# satstep2660.net
KiCad netlist of a schematic drawn in EAGLE
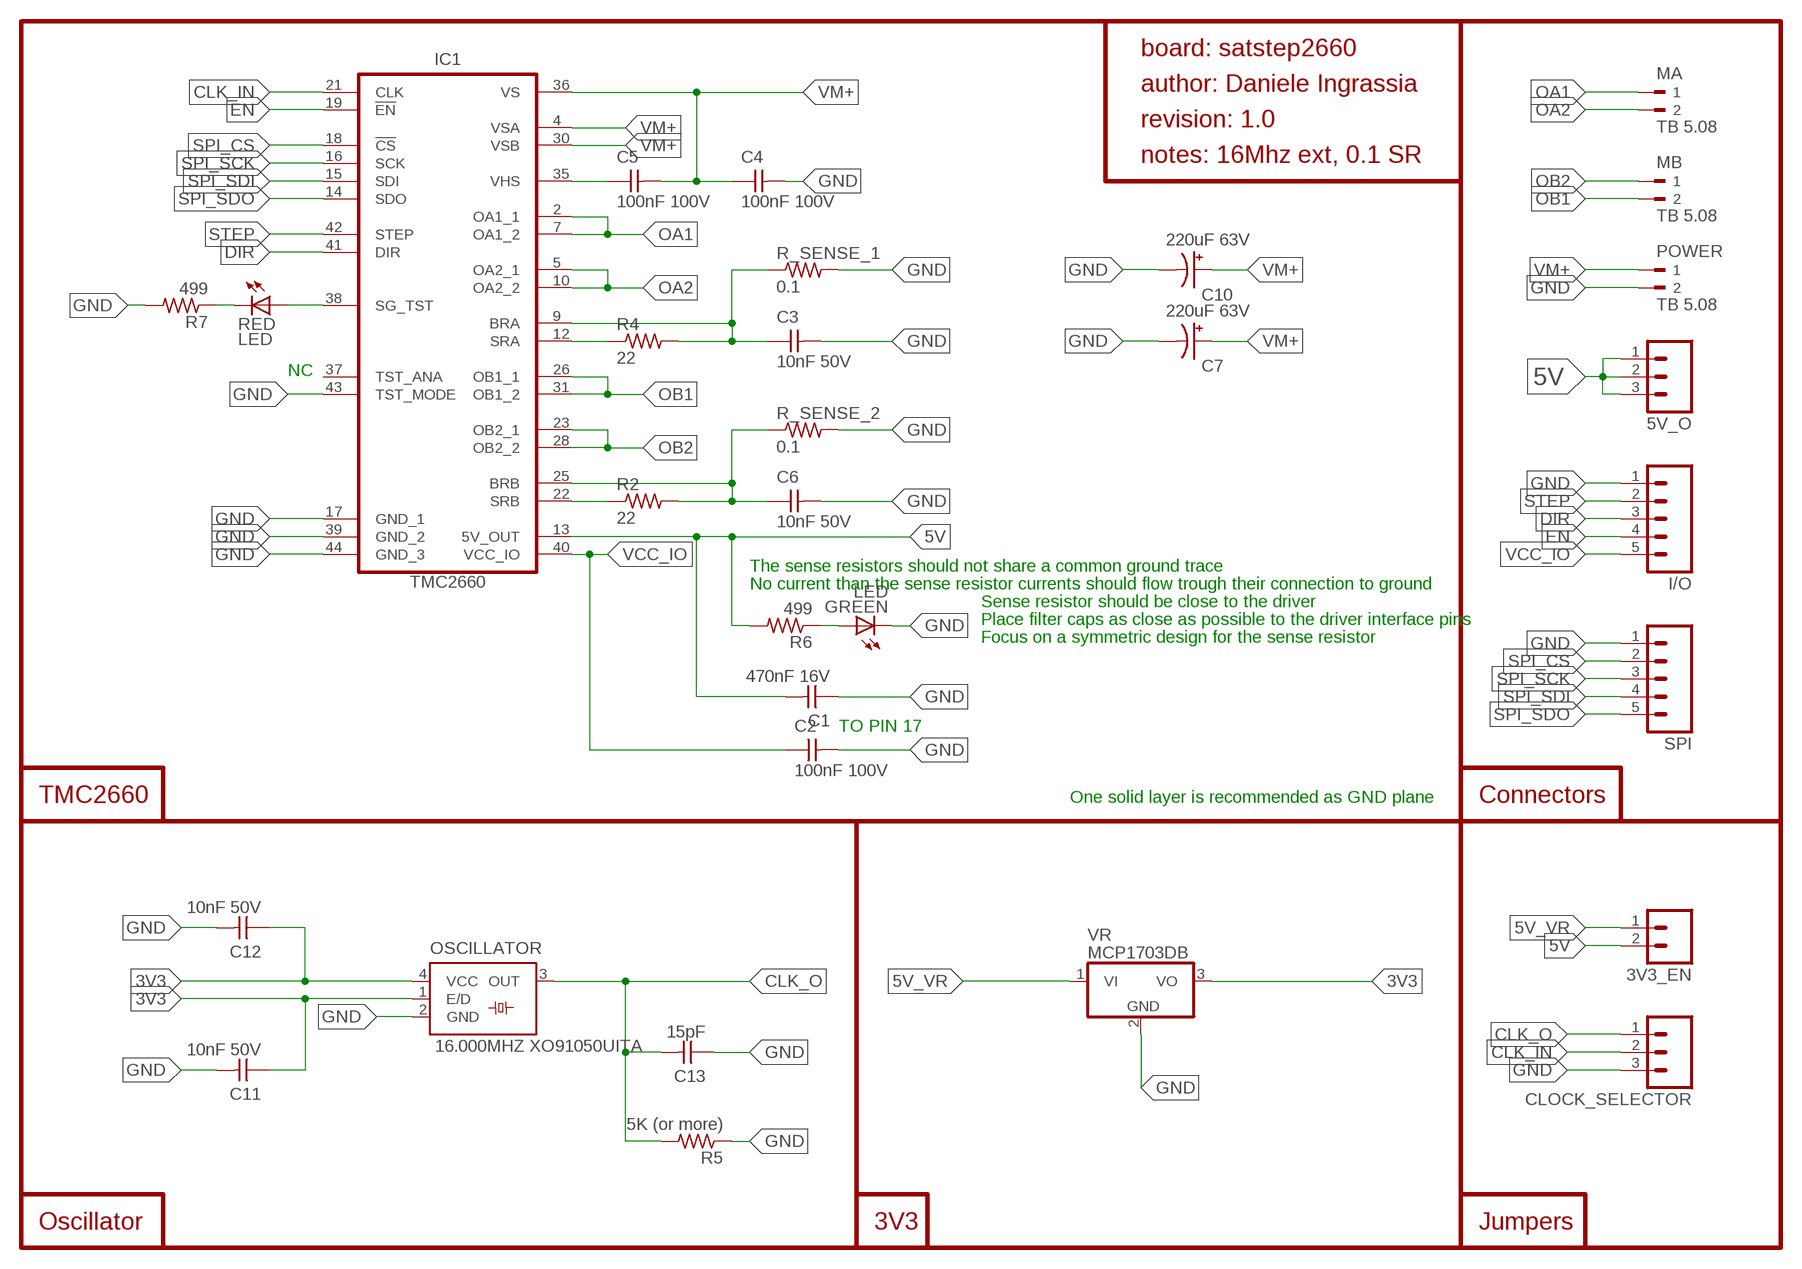
[diagram p0: schematic, sheet 1]

(export (version "E")
  (design (tool "Eeschema 10.0.6"))
  (components
    (comp (ref "3V3_EN")
      (value "M02")
      (footprint "eagle-import:02P")
      (libsource (lib "eagle-import") (part "M02"))
    )
    (comp (ref "5V_O")
      (value "M03")
      (footprint "eagle-import:03P")
      (libsource (lib "eagle-import") (part "M03"))
    )
    (comp (ref "C1")
      (value "470nF 16V")
      (footprint "eagle-import:C1206")
      (libsource (lib "eagle-import") (part "CAP-UNPOLARIZED"))
    )
    (comp (ref "C2")
      (value "100nF 100V")
      (footprint "eagle-import:C1206")
      (libsource (lib "eagle-import") (part "CAP-UNPOLARIZED"))
    )
    (comp (ref "C3")
      (value "10nF 50V")
      (footprint "eagle-import:C1206")
      (libsource (lib "eagle-import") (part "CAP-UNPOLARIZED"))
    )
    (comp (ref "C4")
      (value "100nF 100V")
      (footprint "eagle-import:C1206")
      (libsource (lib "eagle-import") (part "CAP-UNPOLARIZED"))
    )
    (comp (ref "C5")
      (value "100nF 100V")
      (footprint "eagle-import:C1206")
      (libsource (lib "eagle-import") (part "CAP-UNPOLARIZED"))
    )
    (comp (ref "C6")
      (value "10nF 50V")
      (footprint "eagle-import:C1206")
      (libsource (lib "eagle-import") (part "CAP-UNPOLARIZED"))
    )
    (comp (ref "C7")
      (value "220uF 63V")
      (footprint "eagle-import:CPOL-RADIAL-5MM-10MM")
      (libsource (lib "eagle-import") (part "1000UF-RADIAL-5MM-25V-20%"))
    )
    (comp (ref "C10")
      (value "220uF 63V")
      (footprint "eagle-import:CPOL-RADIAL-5MM-10MM")
      (libsource (lib "eagle-import") (part "1000UF-RADIAL-5MM-25V-20%"))
    )
    (comp (ref "C11")
      (value "10nF 50V")
      (footprint "eagle-import:C1206")
      (libsource (lib "eagle-import") (part "CAP-UNPOLARIZED"))
    )
    (comp (ref "C12")
      (value "10nF 50V")
      (footprint "eagle-import:C1206")
      (libsource (lib "eagle-import") (part "CAP-UNPOLARIZED"))
    )
    (comp (ref "C13")
      (value "15pF")
      (footprint "eagle-import:C1206")
      (libsource (lib "eagle-import") (part "CAP-UNPOLARIZED"))
    )
    (comp (ref "CLOCK_SELECTOR")
      (value "M03")
      (footprint "eagle-import:03P")
      (libsource (lib "eagle-import") (part "M03"))
    )
    (comp (ref "GREEN")
      (value "LED")
      (footprint "eagle-import:LED1206")
      (libsource (lib "eagle-import") (part "LED"))
    )
    (comp (ref "I/O")
      (value "M05")
      (footprint "eagle-import:05P")
      (libsource (lib "eagle-import") (part "M05"))
    )
    (comp (ref "IC1")
      (value "TMC2660")
      (footprint "eagle-import:TMC_PQFP44_0.8_10X10_TMC236")
      (fields (field (name "MANUFACTURER") " TRINAMIC "))
      (libsource (lib "eagle-import") (part "TMC2660-PA"))
    )
    (comp (ref "MA")
      (value "TB 5.08")
      (footprint "eagle-import:WEIDMULLER_PM5.08_2")
      (fields (field (name "MPN") "PM5.08/2/90 BLK"))
      (libsource (lib "eagle-import") (part "PM5.08/2/90BLK"))
    )
    (comp (ref "MB")
      (value "TB 5.08")
      (footprint "eagle-import:WEIDMULLER_PM5.08_2")
      (fields (field (name "MPN") "PM5.08/2/90 BLK"))
      (libsource (lib "eagle-import") (part "PM5.08/2/90BLK"))
    )
    (comp (ref "OSCILLATOR")
      (value "16.000MHZ XO91050UITA")
      (footprint "eagle-import:SM77H")
      (libsource (lib "eagle-import") (part "SM77H"))
    )
    (comp (ref "POWER")
      (value "TB 5.08")
      (footprint "eagle-import:WEIDMULLER_PM5.08_2")
      (fields (field (name "MPN") "PM5.08/2/90 BLK"))
      (libsource (lib "eagle-import") (part "PM5.08/2/90BLK"))
    )
    (comp (ref "R2")
      (value "22")
      (footprint "eagle-import:R1206")
      (libsource (lib "eagle-import") (part "RES-US1206"))
    )
    (comp (ref "R4")
      (value "22")
      (footprint "eagle-import:R1206")
      (libsource (lib "eagle-import") (part "RES-US1206"))
    )
    (comp (ref "R5")
      (value "5K (or more)")
      (footprint "eagle-import:R1206")
      (libsource (lib "eagle-import") (part "RES-US1206"))
    )
    (comp (ref "R6")
      (value "499")
      (footprint "eagle-import:R1206")
      (libsource (lib "eagle-import") (part "RES-US1206"))
    )
    (comp (ref "R7")
      (value "499")
      (footprint "eagle-import:R1206")
      (libsource (lib "eagle-import") (part "RES-US1206"))
    )
    (comp (ref "RED")
      (value "LED")
      (footprint "eagle-import:LED1206")
      (libsource (lib "eagle-import") (part "LED"))
    )
    (comp (ref "R_SENSE_1")
      (value "0.1")
      (footprint "eagle-import:R1206")
      (libsource (lib "eagle-import") (part "RES-US1206"))
    )
    (comp (ref "R_SENSE_2")
      (value "0.1")
      (footprint "eagle-import:R1206")
      (libsource (lib "eagle-import") (part "RES-US1206"))
    )
    (comp (ref "SPI")
      (value "M05")
      (footprint "eagle-import:05P")
      (libsource (lib "eagle-import") (part "M05"))
    )
    (comp (ref "VR")
      (value "MCP1703DB")
      (footprint "eagle-import:SOT223")
      (libsource (lib "eagle-import") (part "MCP1703DB"))
    )
  )
  (nets
    (net (code "1") (name "3V3") (class "Default")
      (node (ref "C11") (pin "1") (pinfunction "1_1") (pintype "passive"))
      (node (ref "C12") (pin "1") (pinfunction "1_1") (pintype "passive"))
      (node (ref "OSCILLATOR") (pin "1") (pinfunction "E/D_1") (pintype "input"))
      (node (ref "OSCILLATOR") (pin "4") (pinfunction "VCC_4") (pintype "power_in"))
      (node (ref "VR") (pin "3") (pinfunction "VO_3") (pintype "passive"))
    )
    (net (code "2") (name "5V") (class "Default")
      (node (ref "3V3_EN") (pin "2") (pinfunction "2_2") (pintype "passive"))
      (node (ref "5V_O") (pin "1") (pinfunction "1_1") (pintype "passive"))
      (node (ref "5V_O") (pin "2") (pinfunction "2_2") (pintype "passive"))
      (node (ref "5V_O") (pin "3") (pinfunction "3_3") (pintype "passive"))
      (node (ref "C1") (pin "2") (pinfunction "2_2") (pintype "passive"))
      (node (ref "IC1") (pin "13") (pinfunction "5V_OUT_13") (pintype "output"))
      (node (ref "R6") (pin "2") (pinfunction "2_2") (pintype "passive"))
    )
    (net (code "3") (name "5V_VR") (class "Default")
      (node (ref "3V3_EN") (pin "1") (pinfunction "1_1") (pintype "passive"))
      (node (ref "VR") (pin "1") (pinfunction "VI_1") (pintype "input"))
    )
    (net (code "4") (name "CLK_IN") (class "Default")
      (node (ref "CLOCK_SELECTOR") (pin "2") (pinfunction "2_2") (pintype "passive"))
      (node (ref "IC1") (pin "21") (pinfunction "CLK_21") (pintype "input"))
    )
    (net (code "5") (name "CLK_O") (class "Default")
      (node (ref "C13") (pin "2") (pinfunction "2_2") (pintype "passive"))
      (node (ref "CLOCK_SELECTOR") (pin "1") (pinfunction "1_1") (pintype "passive"))
      (node (ref "OSCILLATOR") (pin "3") (pinfunction "OUT_3") (pintype "output"))
      (node (ref "R5") (pin "2") (pinfunction "2_2") (pintype "passive"))
    )
    (net (code "6") (name "DIR") (class "Default")
      (node (ref "I/O") (pin "3") (pinfunction "3_3") (pintype "passive"))
      (node (ref "IC1") (pin "41") (pinfunction "DIR_41") (pintype "input"))
    )
    (net (code "7") (name "EN") (class "Default")
      (node (ref "I/O") (pin "4") (pinfunction "4_4") (pintype "passive"))
      (node (ref "IC1") (pin "19") (pinfunction "~{EN}_19") (pintype "input"))
    )
    (net (code "8") (name "GND") (class "Default")
      (node (ref "C1") (pin "1") (pinfunction "1_1") (pintype "passive"))
      (node (ref "C10") (pin "-") (pinfunction "-_-") (pintype "passive"))
      (node (ref "C11") (pin "2") (pinfunction "2_2") (pintype "passive"))
      (node (ref "C12") (pin "2") (pinfunction "2_2") (pintype "passive"))
      (node (ref "C13") (pin "1") (pinfunction "1_1") (pintype "passive"))
      (node (ref "C2") (pin "2") (pinfunction "2_2") (pintype "passive"))
      (node (ref "C3") (pin "2") (pinfunction "2_2") (pintype "passive"))
      (node (ref "C4") (pin "2") (pinfunction "2_2") (pintype "passive"))
      (node (ref "C6") (pin "2") (pinfunction "2_2") (pintype "passive"))
      (node (ref "C7") (pin "-") (pinfunction "-_-") (pintype "passive"))
      (node (ref "CLOCK_SELECTOR") (pin "3") (pinfunction "3_3") (pintype "passive"))
      (node (ref "GREEN") (pin "2") (pinfunction "C_2") (pintype "passive"))
      (node (ref "I/O") (pin "1") (pinfunction "1_1") (pintype "passive"))
      (node (ref "IC1") (pin "17") (pinfunction "GND_1_17") (pintype "power_in"))
      (node (ref "IC1") (pin "39") (pinfunction "GND_2_39") (pintype "power_in"))
      (node (ref "IC1") (pin "43") (pinfunction "TST_MODE_43") (pintype "input"))
      (node (ref "IC1") (pin "44") (pinfunction "GND_3_44") (pintype "power_in"))
      (node (ref "OSCILLATOR") (pin "2") (pinfunction "GND_2") (pintype "power_in"))
      (node (ref "POWER") (pin "2") (pinfunction "2_2") (pintype "passive"))
      (node (ref "R5") (pin "1") (pinfunction "1_1") (pintype "passive"))
      (node (ref "R7") (pin "2") (pinfunction "2_2") (pintype "passive"))
      (node (ref "R_SENSE_1") (pin "2") (pinfunction "2_2") (pintype "passive"))
      (node (ref "R_SENSE_2") (pin "2") (pinfunction "2_2") (pintype "passive"))
      (node (ref "SPI") (pin "1") (pinfunction "1_1") (pintype "passive"))
      (node (ref "VR") (pin "2") (pinfunction "GND_2") (pintype "passive"))
    )
    (net (code "9") (name "Net-(GREEN-A)") (class "Default")
      (node (ref "GREEN") (pin "1") (pinfunction "A_1") (pintype "passive"))
      (node (ref "R6") (pin "1") (pinfunction "1_1") (pintype "passive"))
    )
    (net (code "10") (name "Net-(IC1-BRA)") (class "Default")
      (node (ref "C3") (pin "1") (pinfunction "1_1") (pintype "passive"))
      (node (ref "IC1") (pin "9") (pinfunction "BRA_9") (pintype "input"))
      (node (ref "R4") (pin "2") (pinfunction "2_2") (pintype "passive"))
      (node (ref "R_SENSE_1") (pin "1") (pinfunction "1_1") (pintype "passive"))
    )
    (net (code "11") (name "Net-(IC1-BRB)") (class "Default")
      (node (ref "C6") (pin "1") (pinfunction "1_1") (pintype "passive"))
      (node (ref "IC1") (pin "25") (pinfunction "BRB_25") (pintype "input"))
      (node (ref "R2") (pin "2") (pinfunction "2_2") (pintype "passive"))
      (node (ref "R_SENSE_2") (pin "1") (pinfunction "1_1") (pintype "passive"))
    )
    (net (code "12") (name "Net-(IC1-SG_TST)") (class "Default")
      (node (ref "IC1") (pin "38") (pinfunction "SG_TST_38") (pintype "output"))
      (node (ref "RED") (pin "1") (pinfunction "A_1") (pintype "passive"))
    )
    (net (code "13") (name "Net-(IC1-SRA)") (class "Default")
      (node (ref "IC1") (pin "12") (pinfunction "SRA_12") (pintype "input"))
      (node (ref "R4") (pin "1") (pinfunction "1_1") (pintype "passive"))
    )
    (net (code "14") (name "Net-(IC1-SRB)") (class "Default")
      (node (ref "IC1") (pin "22") (pinfunction "SRB_22") (pintype "input"))
      (node (ref "R2") (pin "1") (pinfunction "1_1") (pintype "passive"))
    )
    (net (code "15") (name "Net-(IC1-VHS)") (class "Default")
      (node (ref "C5") (pin "1") (pinfunction "1_1") (pintype "passive"))
      (node (ref "IC1") (pin "35") (pinfunction "VHS_35") (pintype "power_in"))
    )
    (net (code "16") (name "Net-(RED-C)") (class "Default")
      (node (ref "R7") (pin "1") (pinfunction "1_1") (pintype "passive"))
      (node (ref "RED") (pin "2") (pinfunction "C_2") (pintype "passive"))
    )
    (net (code "17") (name "OA1") (class "Default")
      (node (ref "IC1") (pin "2") (pinfunction "OA1_1_2") (pintype "output"))
      (node (ref "IC1") (pin "7") (pinfunction "OA1_2_7") (pintype "output"))
      (node (ref "MA") (pin "1") (pinfunction "1_1") (pintype "passive"))
    )
    (net (code "18") (name "OA2") (class "Default")
      (node (ref "IC1") (pin "10") (pinfunction "OA2_2_10") (pintype "output"))
      (node (ref "IC1") (pin "5") (pinfunction "OA2_1_5") (pintype "output"))
      (node (ref "MA") (pin "2") (pinfunction "2_2") (pintype "passive"))
    )
    (net (code "19") (name "OB1") (class "Default")
      (node (ref "IC1") (pin "26") (pinfunction "OB1_1_26") (pintype "output"))
      (node (ref "IC1") (pin "31") (pinfunction "OB1_2_31") (pintype "output"))
      (node (ref "MB") (pin "2") (pinfunction "2_2") (pintype "passive"))
    )
    (net (code "20") (name "OB2") (class "Default")
      (node (ref "IC1") (pin "23") (pinfunction "OB2_1_23") (pintype "output"))
      (node (ref "IC1") (pin "28") (pinfunction "OB2_2_28") (pintype "output"))
      (node (ref "MB") (pin "1") (pinfunction "1_1") (pintype "passive"))
    )
    (net (code "21") (name "SPI_CS") (class "Default")
      (node (ref "IC1") (pin "18") (pinfunction "~{CS}_18") (pintype "input"))
      (node (ref "SPI") (pin "2") (pinfunction "2_2") (pintype "passive"))
    )
    (net (code "22") (name "SPI_SCK") (class "Default")
      (node (ref "IC1") (pin "16") (pinfunction "SCK_16") (pintype "input"))
      (node (ref "SPI") (pin "3") (pinfunction "3_3") (pintype "passive"))
    )
    (net (code "23") (name "SPI_SDI") (class "Default")
      (node (ref "IC1") (pin "15") (pinfunction "SDI_15") (pintype "input"))
      (node (ref "SPI") (pin "4") (pinfunction "4_4") (pintype "passive"))
    )
    (net (code "24") (name "SPI_SDO") (class "Default")
      (node (ref "IC1") (pin "14") (pinfunction "SDO_14") (pintype "output"))
      (node (ref "SPI") (pin "5") (pinfunction "5_5") (pintype "passive"))
    )
    (net (code "25") (name "STEP") (class "Default")
      (node (ref "I/O") (pin "2") (pinfunction "2_2") (pintype "passive"))
      (node (ref "IC1") (pin "42") (pinfunction "STEP_42") (pintype "input"))
    )
    (net (code "26") (name "VCC_IO") (class "Default")
      (node (ref "C2") (pin "1") (pinfunction "1_1") (pintype "passive"))
      (node (ref "I/O") (pin "5") (pinfunction "5_5") (pintype "passive"))
      (node (ref "IC1") (pin "40") (pinfunction "VCC_IO_40") (pintype "power_in"))
    )
    (net (code "27") (name "VM+") (class "Default")
      (node (ref "C10") (pin "+") (pinfunction "+_+") (pintype "passive"))
      (node (ref "C4") (pin "1") (pinfunction "1_1") (pintype "passive"))
      (node (ref "C5") (pin "2") (pinfunction "2_2") (pintype "passive"))
      (node (ref "C7") (pin "+") (pinfunction "+_+") (pintype "passive"))
      (node (ref "IC1") (pin "30") (pinfunction "VSB_30") (pintype "input"))
      (node (ref "IC1") (pin "36") (pinfunction "VS_36") (pintype "power_in"))
      (node (ref "IC1") (pin "4") (pinfunction "VSA_4") (pintype "input"))
      (node (ref "POWER") (pin "1") (pinfunction "1_1") (pintype "passive"))
    )
    (net (code "28") (name "unconnected-(IC1-TST_ANA-Pad37)") (class "Default")
      (node (ref "IC1") (pin "37") (pinfunction "TST_ANA_37") (pintype "output"))
    )
  )
)
